# Pyr0-Piezo_SingleDisk_Adapter_2pin.net
KiCad netlist of a schematic drawn in EAGLE
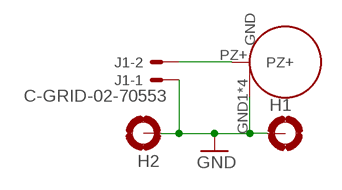
[diagram p0: schematic, sheet 1]

(export (version "E")
  (design (tool "Eeschema 10.0.6"))
  (components
    (comp (ref "H1")
      (value "HOLES_MOUNT-PAD-ROUND3.2")
      (footprint "eagle-import:HOLES_3,2-PAD")
      (libsource (lib "eagle-import") (part "HOLES_MOUNT-PAD-ROUND3.2"))
    )
    (comp (ref "H2")
      (value "HOLES_MOUNT-PAD-ROUND3.2")
      (footprint "eagle-import:HOLES_3,2-PAD")
      (libsource (lib "eagle-import") (part "HOLES_MOUNT-PAD-ROUND3.2"))
    )
    (comp (ref "J1")
      (value "C-GRID-02-70553")
      (footprint "eagle-import:70553-02")
      (fields (field (name "MF") "MOLEX"))
      (libsource (lib "eagle-import") (part "C-GRID-02-70553"))
    )
    (comp (ref "PZ1")
      (value "PIEZO-DISK12MM")
      (footprint "eagle-import:PIEZO-DISK-12MM")
      (libsource (lib "eagle-import") (part "PIEZO-DISK12MM"))
    )
  )
  (nets
    (net (code "1") (name "GND") (class "Default")
      (node (ref "H1") (pin "B3,2") (pinfunction "MOUNT_B3,2") (pintype "passive"))
      (node (ref "H2") (pin "B3,2") (pinfunction "MOUNT_B3,2") (pintype "passive"))
      (node (ref "J1") (pin "1") (pinfunction "S_1") (pintype "passive"))
      (node (ref "PZ1") (pin "GND1") (pinfunction "GND_GND1") (pintype "passive"))
      (node (ref "PZ1") (pin "GND2") (pinfunction "GND_GND2") (pintype "passive"))
      (node (ref "PZ1") (pin "GND3") (pinfunction "GND_GND3") (pintype "passive"))
      (node (ref "PZ1") (pin "GND4") (pinfunction "GND_GND4") (pintype "passive"))
    )
    (net (code "2") (name "Net-(J1B-S)") (class "Default")
      (node (ref "J1") (pin "2") (pinfunction "S_2") (pintype "passive"))
      (node (ref "PZ1") (pin "PZ+") (pinfunction "PZ+_PZ+") (pintype "bidirectional"))
    )
  )
)
